# tattooboard.net
KiCad netlist of a schematic drawn in EAGLE
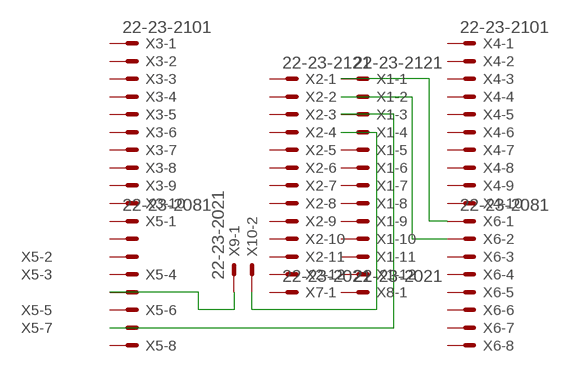
[diagram p0: schematic, sheet 1]

(export (version "E")
  (design (tool "Eeschema 10.0.6"))
  (components
    (comp (ref "X1")
      (value "22-23-2121")
      (footprint "eagle-import:22-23-2121")
      (fields (field (name "MF") "MOLEX"))
      (libsource (lib "eagle-import") (part "22-23-2121"))
    )
    (comp (ref "X2")
      (value "22-23-2121")
      (footprint "eagle-import:22-23-2121")
      (fields (field (name "MF") "MOLEX"))
      (libsource (lib "eagle-import") (part "22-23-2121"))
    )
    (comp (ref "X3")
      (value "22-23-2101")
      (footprint "eagle-import:22-23-2101")
      (fields (field (name "MF") "MOLEX"))
      (libsource (lib "eagle-import") (part "22-23-2101"))
    )
    (comp (ref "X4")
      (value "22-23-2101")
      (footprint "eagle-import:22-23-2101")
      (fields (field (name "MF") "MOLEX"))
      (libsource (lib "eagle-import") (part "22-23-2101"))
    )
    (comp (ref "X5")
      (value "22-23-2081")
      (footprint "eagle-import:22-23-2081")
      (fields (field (name "MF") "MOLEX"))
      (libsource (lib "eagle-import") (part "22-23-2081"))
    )
    (comp (ref "X6")
      (value "22-23-2081")
      (footprint "eagle-import:22-23-2081")
      (fields (field (name "MF") "MOLEX"))
      (libsource (lib "eagle-import") (part "22-23-2081"))
    )
    (comp (ref "X7")
      (value "22-23-2021")
      (footprint "eagle-import:22-23-2021")
      (fields (field (name "MF") "MOLEX"))
      (libsource (lib "eagle-import") (part "22-23-2021"))
    )
    (comp (ref "X8")
      (value "22-23-2021")
      (footprint "eagle-import:22-23-2021")
      (fields (field (name "MF") "MOLEX"))
      (libsource (lib "eagle-import") (part "22-23-2021"))
    )
    (comp (ref "X9")
      (value "22-23-2021")
      (footprint "eagle-import:22-23-2021")
      (fields (field (name "MF") "MOLEX"))
      (libsource (lib "eagle-import") (part "22-23-2021"))
    )
    (comp (ref "X10")
      (value "22-23-2021")
      (footprint "eagle-import:22-23-2021")
      (fields (field (name "MF") "MOLEX"))
      (libsource (lib "eagle-import") (part "22-23-2021"))
    )
  )
  (nets
    (net (code "1") (name "Net-(X1A-S)") (class "Default")
      (node (ref "X1") (pin "1") (pinfunction "S_1") (pintype "passive"))
      (node (ref "X6") (pin "1") (pinfunction "S_1") (pintype "passive"))
    )
    (net (code "2") (name "Net-(X1E-S)") (class "Default")
      (node (ref "X1") (pin "2") (pinfunction "S_2") (pintype "passive"))
      (node (ref "X6") (pin "2") (pinfunction "S_2") (pintype "passive"))
    )
    (net (code "3") (name "Net-(X1F-S)") (class "Default")
      (node (ref "X1") (pin "3") (pinfunction "S_3") (pintype "passive"))
      (node (ref "X5") (pin "7") (pinfunction "S_7") (pintype "passive"))
    )
    (net (code "4") (name "Net-(X5E-S)") (class "Default")
      (node (ref "X5") (pin "5") (pinfunction "S_5") (pintype "passive"))
      (node (ref "X9") (pin "1") (pinfunction "S_1") (pintype "passive"))
    )
    (net (code "5") (name "Net-(X10B-S)") (class "Default")
      (node (ref "X1") (pin "4") (pinfunction "S_4") (pintype "passive"))
      (node (ref "X10") (pin "2") (pinfunction "S_2") (pintype "passive"))
    )
    (net (code "6") (name "unconnected-(X1B-S-Pad10)") (class "Default")
      (node (ref "X1") (pin "10") (pinfunction "S_10") (pintype "passive"))
    )
    (net (code "7") (name "unconnected-(X1C-S-Pad11)") (class "Default")
      (node (ref "X1") (pin "11") (pinfunction "S_11") (pintype "passive"))
    )
    (net (code "8") (name "unconnected-(X1D-S-Pad12)") (class "Default")
      (node (ref "X1") (pin "12") (pinfunction "S_12") (pintype "passive"))
    )
    (net (code "9") (name "unconnected-(X1H-S-Pad5)") (class "Default")
      (node (ref "X1") (pin "5") (pinfunction "S_5") (pintype "passive"))
    )
    (net (code "10") (name "unconnected-(X1I-S-Pad6)") (class "Default")
      (node (ref "X1") (pin "6") (pinfunction "S_6") (pintype "passive"))
    )
    (net (code "11") (name "unconnected-(X1J-S-Pad7)") (class "Default")
      (node (ref "X1") (pin "7") (pinfunction "S_7") (pintype "passive"))
    )
    (net (code "12") (name "unconnected-(X1K-S-Pad8)") (class "Default")
      (node (ref "X1") (pin "8") (pinfunction "S_8") (pintype "passive"))
    )
    (net (code "13") (name "unconnected-(X1L-S-Pad9)") (class "Default")
      (node (ref "X1") (pin "9") (pinfunction "S_9") (pintype "passive"))
    )
    (net (code "14") (name "unconnected-(X2A-S-Pad1)") (class "Default")
      (node (ref "X2") (pin "1") (pinfunction "S_1") (pintype "passive"))
    )
    (net (code "15") (name "unconnected-(X2B-S-Pad10)") (class "Default")
      (node (ref "X2") (pin "10") (pinfunction "S_10") (pintype "passive"))
    )
    (net (code "16") (name "unconnected-(X2C-S-Pad11)") (class "Default")
      (node (ref "X2") (pin "11") (pinfunction "S_11") (pintype "passive"))
    )
    (net (code "17") (name "unconnected-(X2D-S-Pad12)") (class "Default")
      (node (ref "X2") (pin "12") (pinfunction "S_12") (pintype "passive"))
    )
    (net (code "18") (name "unconnected-(X2E-S-Pad2)") (class "Default")
      (node (ref "X2") (pin "2") (pinfunction "S_2") (pintype "passive"))
    )
    (net (code "19") (name "unconnected-(X2F-S-Pad3)") (class "Default")
      (node (ref "X2") (pin "3") (pinfunction "S_3") (pintype "passive"))
    )
    (net (code "20") (name "unconnected-(X2G-S-Pad4)") (class "Default")
      (node (ref "X2") (pin "4") (pinfunction "S_4") (pintype "passive"))
    )
    (net (code "21") (name "unconnected-(X2H-S-Pad5)") (class "Default")
      (node (ref "X2") (pin "5") (pinfunction "S_5") (pintype "passive"))
    )
    (net (code "22") (name "unconnected-(X2I-S-Pad6)") (class "Default")
      (node (ref "X2") (pin "6") (pinfunction "S_6") (pintype "passive"))
    )
    (net (code "23") (name "unconnected-(X2J-S-Pad7)") (class "Default")
      (node (ref "X2") (pin "7") (pinfunction "S_7") (pintype "passive"))
    )
    (net (code "24") (name "unconnected-(X2K-S-Pad8)") (class "Default")
      (node (ref "X2") (pin "8") (pinfunction "S_8") (pintype "passive"))
    )
    (net (code "25") (name "unconnected-(X2L-S-Pad9)") (class "Default")
      (node (ref "X2") (pin "9") (pinfunction "S_9") (pintype "passive"))
    )
    (net (code "26") (name "unconnected-(X3A-S-Pad1)") (class "Default")
      (node (ref "X3") (pin "1") (pinfunction "S_1") (pintype "passive"))
    )
    (net (code "27") (name "unconnected-(X3B-S-Pad10)") (class "Default")
      (node (ref "X3") (pin "10") (pinfunction "S_10") (pintype "passive"))
    )
    (net (code "28") (name "unconnected-(X3C-S-Pad2)") (class "Default")
      (node (ref "X3") (pin "2") (pinfunction "S_2") (pintype "passive"))
    )
    (net (code "29") (name "unconnected-(X3D-S-Pad3)") (class "Default")
      (node (ref "X3") (pin "3") (pinfunction "S_3") (pintype "passive"))
    )
    (net (code "30") (name "unconnected-(X3E-S-Pad4)") (class "Default")
      (node (ref "X3") (pin "4") (pinfunction "S_4") (pintype "passive"))
    )
    (net (code "31") (name "unconnected-(X3F-S-Pad5)") (class "Default")
      (node (ref "X3") (pin "5") (pinfunction "S_5") (pintype "passive"))
    )
    (net (code "32") (name "unconnected-(X3G-S-Pad6)") (class "Default")
      (node (ref "X3") (pin "6") (pinfunction "S_6") (pintype "passive"))
    )
    (net (code "33") (name "unconnected-(X3H-S-Pad7)") (class "Default")
      (node (ref "X3") (pin "7") (pinfunction "S_7") (pintype "passive"))
    )
    (net (code "34") (name "unconnected-(X3I-S-Pad8)") (class "Default")
      (node (ref "X3") (pin "8") (pinfunction "S_8") (pintype "passive"))
    )
    (net (code "35") (name "unconnected-(X3J-S-Pad9)") (class "Default")
      (node (ref "X3") (pin "9") (pinfunction "S_9") (pintype "passive"))
    )
    (net (code "36") (name "unconnected-(X4A-S-Pad1)") (class "Default")
      (node (ref "X4") (pin "1") (pinfunction "S_1") (pintype "passive"))
    )
    (net (code "37") (name "unconnected-(X4B-S-Pad10)") (class "Default")
      (node (ref "X4") (pin "10") (pinfunction "S_10") (pintype "passive"))
    )
    (net (code "38") (name "unconnected-(X4C-S-Pad2)") (class "Default")
      (node (ref "X4") (pin "2") (pinfunction "S_2") (pintype "passive"))
    )
    (net (code "39") (name "unconnected-(X4D-S-Pad3)") (class "Default")
      (node (ref "X4") (pin "3") (pinfunction "S_3") (pintype "passive"))
    )
    (net (code "40") (name "unconnected-(X4E-S-Pad4)") (class "Default")
      (node (ref "X4") (pin "4") (pinfunction "S_4") (pintype "passive"))
    )
    (net (code "41") (name "unconnected-(X4F-S-Pad5)") (class "Default")
      (node (ref "X4") (pin "5") (pinfunction "S_5") (pintype "passive"))
    )
    (net (code "42") (name "unconnected-(X4G-S-Pad6)") (class "Default")
      (node (ref "X4") (pin "6") (pinfunction "S_6") (pintype "passive"))
    )
    (net (code "43") (name "unconnected-(X4H-S-Pad7)") (class "Default")
      (node (ref "X4") (pin "7") (pinfunction "S_7") (pintype "passive"))
    )
    (net (code "44") (name "unconnected-(X4I-S-Pad8)") (class "Default")
      (node (ref "X4") (pin "8") (pinfunction "S_8") (pintype "passive"))
    )
    (net (code "45") (name "unconnected-(X4J-S-Pad9)") (class "Default")
      (node (ref "X4") (pin "9") (pinfunction "S_9") (pintype "passive"))
    )
    (net (code "46") (name "unconnected-(X5A-S-Pad1)") (class "Default")
      (node (ref "X5") (pin "1") (pinfunction "S_1") (pintype "passive"))
    )
    (net (code "47") (name "unconnected-(X5B-S-Pad2)") (class "Default")
      (node (ref "X5") (pin "2") (pinfunction "S_2") (pintype "passive"))
    )
    (net (code "48") (name "unconnected-(X5C-S-Pad3)") (class "Default")
      (node (ref "X5") (pin "3") (pinfunction "S_3") (pintype "passive"))
    )
    (net (code "49") (name "unconnected-(X5D-S-Pad4)") (class "Default")
      (node (ref "X5") (pin "4") (pinfunction "S_4") (pintype "passive"))
    )
    (net (code "50") (name "unconnected-(X5F-S-Pad6)") (class "Default")
      (node (ref "X5") (pin "6") (pinfunction "S_6") (pintype "passive"))
    )
    (net (code "51") (name "unconnected-(X5H-S-Pad8)") (class "Default")
      (node (ref "X5") (pin "8") (pinfunction "S_8") (pintype "passive"))
    )
    (net (code "52") (name "unconnected-(X6C-S-Pad3)") (class "Default")
      (node (ref "X6") (pin "3") (pinfunction "S_3") (pintype "passive"))
    )
    (net (code "53") (name "unconnected-(X6D-S-Pad4)") (class "Default")
      (node (ref "X6") (pin "4") (pinfunction "S_4") (pintype "passive"))
    )
    (net (code "54") (name "unconnected-(X6E-S-Pad5)") (class "Default")
      (node (ref "X6") (pin "5") (pinfunction "S_5") (pintype "passive"))
    )
    (net (code "55") (name "unconnected-(X6F-S-Pad6)") (class "Default")
      (node (ref "X6") (pin "6") (pinfunction "S_6") (pintype "passive"))
    )
    (net (code "56") (name "unconnected-(X6G-S-Pad7)") (class "Default")
      (node (ref "X6") (pin "7") (pinfunction "S_7") (pintype "passive"))
    )
    (net (code "57") (name "unconnected-(X6H-S-Pad8)") (class "Default")
      (node (ref "X6") (pin "8") (pinfunction "S_8") (pintype "passive"))
    )
    (net (code "58") (name "unconnected-(X7A-S-Pad1)") (class "Default")
      (node (ref "X7") (pin "1") (pinfunction "S_1") (pintype "passive"))
    )
    (net (code "59") (name "unconnected-(X8A-S-Pad1)") (class "Default")
      (node (ref "X8") (pin "1") (pinfunction "S_1") (pintype "passive"))
    )
  )
)
